# TPS61169_Tant.net
KiCad netlist of a schematic drawn in EAGLE
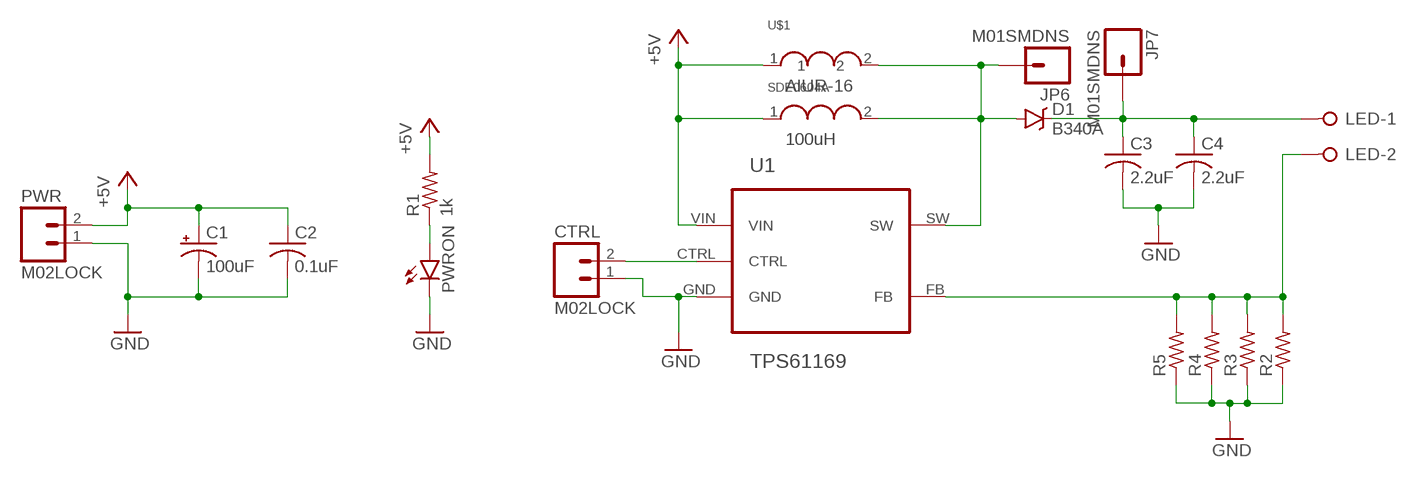
[diagram p0: schematic, sheet 2]

(export (version "E")
  (design (tool "Eeschema 10.0.6"))
  (components
    (comp (ref "AIUR-16")
      (value "100uH")
      (footprint "eagle-import:3MM_LEADS_7MM")
      (libsource (lib "eagle-import") (part "AIUR-16"))
    )
    (comp (ref "C1")
      (value "100uF")
      (footprint "eagle-import:SMC_C")
      (libsource (lib "eagle-import") (part "CPOL-USSMCC"))
    )
    (comp (ref "C2")
      (value "0.1uF")
      (footprint "eagle-import:C0805")
      (libsource (lib "eagle-import") (part "C-USC0805"))
    )
    (comp (ref "C3")
      (value "2.2uF")
      (footprint "eagle-import:C0805")
      (libsource (lib "eagle-import") (part "C-USC0805"))
    )
    (comp (ref "C4")
      (value "2.2uF")
      (footprint "eagle-import:C0805")
      (libsource (lib "eagle-import") (part "C-USC0805"))
    )
    (comp (ref "CTRL")
      (value "M02LOCK")
      (footprint "eagle-import:1X02_LOCK")
      (libsource (lib "eagle-import") (part "M02LOCK"))
    )
    (comp (ref "D1")
      (value "B340A")
      (footprint "eagle-import:SMA-DIODE")
      (libsource (lib "eagle-import") (part "DIODE-SCHOTTKY-B340A"))
    )
    (comp (ref "JP6")
      (value "M01SMDNS")
      (footprint "eagle-import:1X01NS")
      (libsource (lib "eagle-import") (part "M01SMDNS"))
    )
    (comp (ref "JP7")
      (value "M01SMDNS")
      (footprint "eagle-import:1X01NS")
      (libsource (lib "eagle-import") (part "M01SMDNS"))
    )
    (comp (ref "LED")
      (value "W237-02P")
      (footprint "eagle-import:W237-132")
      (libsource (lib "eagle-import") (part "W237-02P"))
    )
    (comp (ref "PWR")
      (value "M02LOCK")
      (footprint "eagle-import:1X02_LOCK")
      (libsource (lib "eagle-import") (part "M02LOCK"))
    )
    (comp (ref "PWRON")
      (value "LED1206")
      (footprint "eagle-import:LED-1206")
      (libsource (lib "eagle-import") (part "LED1206"))
    )
    (comp (ref "R1")
      (value "1k")
      (footprint "eagle-import:R0805")
      (libsource (lib "eagle-import") (part "R-US_R0805"))
    )
    (comp (ref "R2")
      (value "R-US_R0805")
      (footprint "eagle-import:R0805")
      (libsource (lib "eagle-import") (part "R-US_R0805"))
    )
    (comp (ref "R3")
      (value "R-US_R0805")
      (footprint "eagle-import:R0805")
      (libsource (lib "eagle-import") (part "R-US_R0805"))
    )
    (comp (ref "R4")
      (value "R-US_R0805")
      (footprint "eagle-import:R0805")
      (libsource (lib "eagle-import") (part "R-US_R0805"))
    )
    (comp (ref "R5")
      (value "R-US_R0805")
      (footprint "eagle-import:R0805")
      (libsource (lib "eagle-import") (part "R-US_R0805"))
    )
    (comp (ref "U$1")
      (value "SDE0604A")
      (footprint "eagle-import:BOURNS_SMD")
      (libsource (lib "eagle-import") (part "SDE0604A"))
    )
    (comp (ref "U1")
      (value "TPS61169")
      (footprint "eagle-import:SOT65P210X110-5N")
      (fields (field (name "MPN") "74AHCT1G04GW/T1"))
      (libsource (lib "eagle-import") (part "74AHCT1G04GW/T1"))
    )
  )
  (nets
    (net (code "1") (name "+5V") (class "Default")
      (node (ref "AIUR-16") (pin "1") (pinfunction "1_1") (pintype "bidirectional"))
      (node (ref "C1") (pin "+") (pinfunction "+_+") (pintype "passive"))
      (node (ref "C2") (pin "1") (pinfunction "1_1") (pintype "passive"))
      (node (ref "PWR") (pin "2") (pinfunction "2_2") (pintype "passive"))
      (node (ref "R1") (pin "2") (pinfunction "2_2") (pintype "passive"))
      (node (ref "U$1") (pin "1") (pinfunction "1_1") (pintype "bidirectional"))
      (node (ref "U1") (pin "VIN") (pinfunction "VIN_VIN") (pintype "power_in"))
    )
    (net (code "2") (name "GND") (class "Default")
      (node (ref "C1") (pin "-") (pinfunction "-_-") (pintype "passive"))
      (node (ref "C2") (pin "2") (pinfunction "2_2") (pintype "passive"))
      (node (ref "C3") (pin "2") (pinfunction "2_2") (pintype "passive"))
      (node (ref "C4") (pin "2") (pinfunction "2_2") (pintype "passive"))
      (node (ref "CTRL") (pin "1") (pinfunction "1_1") (pintype "passive"))
      (node (ref "PWR") (pin "1") (pinfunction "1_1") (pintype "passive"))
      (node (ref "PWRON") (pin "C") (pinfunction "C_C") (pintype "passive"))
      (node (ref "R2") (pin "1") (pinfunction "1_1") (pintype "passive"))
      (node (ref "R3") (pin "1") (pinfunction "1_1") (pintype "passive"))
      (node (ref "R4") (pin "1") (pinfunction "1_1") (pintype "passive"))
      (node (ref "R5") (pin "1") (pinfunction "1_1") (pintype "passive"))
      (node (ref "U1") (pin "GND") (pinfunction "GND_GND") (pintype "power_in"))
    )
    (net (code "3") (name "Net-(AIUR-16-Pad2)") (class "Default")
      (node (ref "AIUR-16") (pin "2") (pinfunction "2_2") (pintype "bidirectional"))
      (node (ref "D1") (pin "A") (pinfunction "A_A") (pintype "passive"))
      (node (ref "JP6") (pin "1") (pinfunction "1_1") (pintype "passive"))
      (node (ref "U$1") (pin "2") (pinfunction "2_2") (pintype "bidirectional"))
      (node (ref "U1") (pin "SW") (pinfunction "SW_SW") (pintype "output"))
    )
    (net (code "4") (name "Net-(CTRL-Pad2)") (class "Default")
      (node (ref "CTRL") (pin "2") (pinfunction "2_2") (pintype "passive"))
      (node (ref "U1") (pin "CTRL") (pinfunction "CTRL_CTRL") (pintype "input"))
    )
    (net (code "5") (name "Net-(LEDA-KL)") (class "Default")
      (node (ref "C3") (pin "1") (pinfunction "1_1") (pintype "passive"))
      (node (ref "C4") (pin "1") (pinfunction "1_1") (pintype "passive"))
      (node (ref "D1") (pin "C") (pinfunction "C_C") (pintype "passive"))
      (node (ref "JP7") (pin "1") (pinfunction "1_1") (pintype "passive"))
      (node (ref "LED") (pin "1") (pinfunction "KL_1") (pintype "passive"))
    )
    (net (code "6") (name "Net-(LEDB-KL)") (class "Default")
      (node (ref "LED") (pin "2") (pinfunction "KL_2") (pintype "passive"))
      (node (ref "R2") (pin "2") (pinfunction "2_2") (pintype "passive"))
      (node (ref "R3") (pin "2") (pinfunction "2_2") (pintype "passive"))
      (node (ref "R4") (pin "2") (pinfunction "2_2") (pintype "passive"))
      (node (ref "R5") (pin "2") (pinfunction "2_2") (pintype "passive"))
      (node (ref "U1") (pin "FB") (pinfunction "FB_FB") (pintype "input"))
    )
    (net (code "7") (name "Net-(PWRON-PadA)") (class "Default")
      (node (ref "PWRON") (pin "A") (pinfunction "A_A") (pintype "passive"))
      (node (ref "R1") (pin "1") (pinfunction "1_1") (pintype "passive"))
    )
  )
)
